# LilyPad_Rainbow_LED_v02.net
KiCad netlist of a schematic drawn in EAGLE
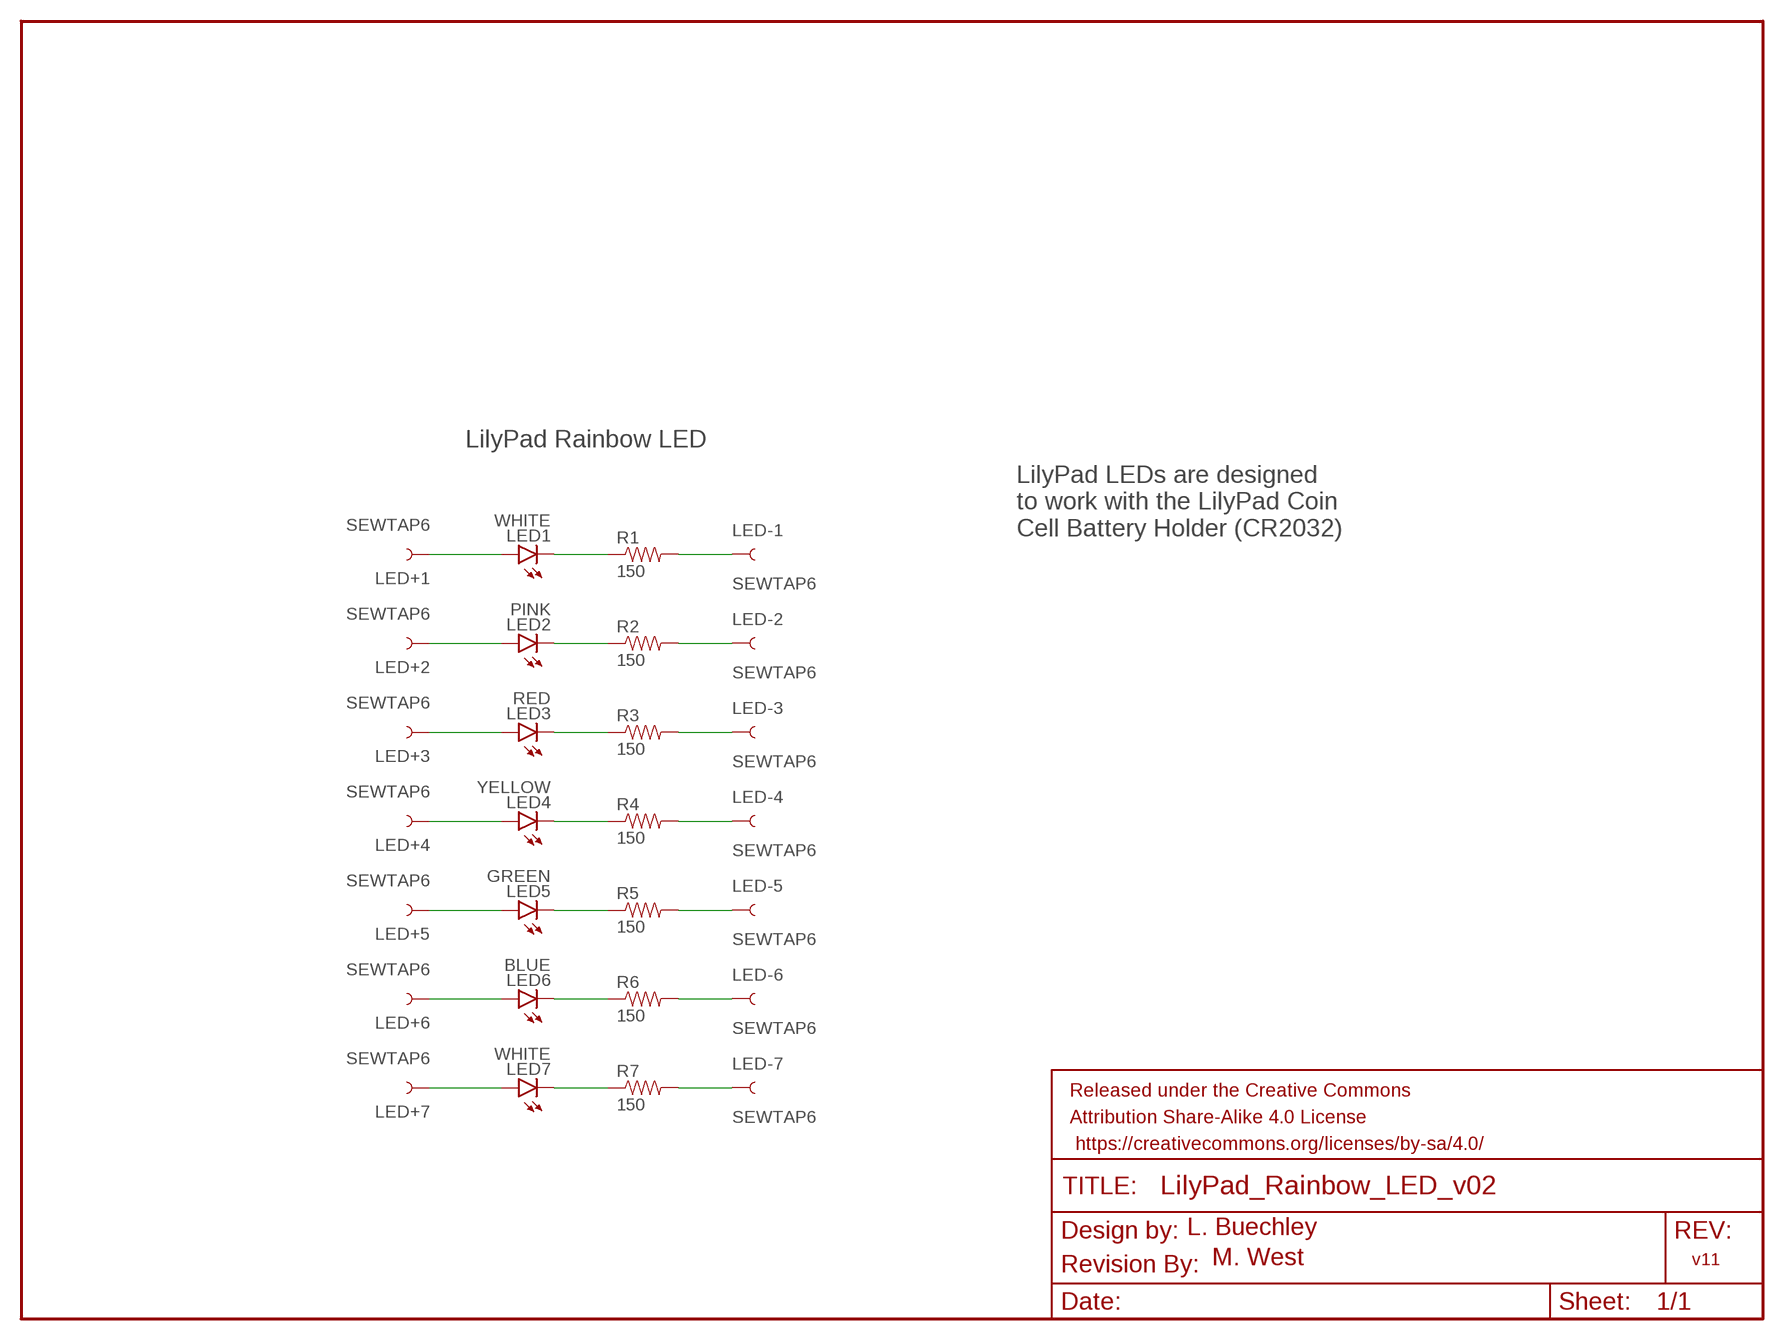
[diagram p0: schematic, sheet 1]

(export (version "E")
  (design (tool "Eeschema 10.0.6"))
  (components
    (comp (ref "FRAME1")
      (value "FRAME-LETTER")
      (footprint "eagle-import:CREATIVE_COMMONS")
      (libsource (lib "eagle-import") (part "FRAME-LETTER"))
    )
    (comp (ref "LED+1")
      (value "SEWTAP6")
      (footprint "eagle-import:PETAL-SMALL-2SIDE")
      (libsource (lib "eagle-import") (part "SEWTAP6"))
    )
    (comp (ref "LED+2")
      (value "SEWTAP6")
      (footprint "eagle-import:PETAL-SMALL-2SIDE")
      (libsource (lib "eagle-import") (part "SEWTAP6"))
    )
    (comp (ref "LED+3")
      (value "SEWTAP6")
      (footprint "eagle-import:PETAL-SMALL-2SIDE")
      (libsource (lib "eagle-import") (part "SEWTAP6"))
    )
    (comp (ref "LED+4")
      (value "SEWTAP6")
      (footprint "eagle-import:PETAL-SMALL-2SIDE")
      (libsource (lib "eagle-import") (part "SEWTAP6"))
    )
    (comp (ref "LED+5")
      (value "SEWTAP6")
      (footprint "eagle-import:PETAL-SMALL-2SIDE")
      (libsource (lib "eagle-import") (part "SEWTAP6"))
    )
    (comp (ref "LED+6")
      (value "SEWTAP6")
      (footprint "eagle-import:PETAL-SMALL-2SIDE")
      (libsource (lib "eagle-import") (part "SEWTAP6"))
    )
    (comp (ref "LED+7")
      (value "SEWTAP6")
      (footprint "eagle-import:PETAL-SMALL-2SIDE")
      (libsource (lib "eagle-import") (part "SEWTAP6"))
    )
    (comp (ref "LED-1")
      (value "SEWTAP6")
      (footprint "eagle-import:PETAL-SMALL-2SIDE")
      (libsource (lib "eagle-import") (part "SEWTAP6"))
    )
    (comp (ref "LED-2")
      (value "SEWTAP6")
      (footprint "eagle-import:PETAL-SMALL-2SIDE")
      (libsource (lib "eagle-import") (part "SEWTAP6"))
    )
    (comp (ref "LED-3")
      (value "SEWTAP6")
      (footprint "eagle-import:PETAL-SMALL-2SIDE")
      (libsource (lib "eagle-import") (part "SEWTAP6"))
    )
    (comp (ref "LED-4")
      (value "SEWTAP6")
      (footprint "eagle-import:PETAL-SMALL-2SIDE")
      (libsource (lib "eagle-import") (part "SEWTAP6"))
    )
    (comp (ref "LED-5")
      (value "SEWTAP6")
      (footprint "eagle-import:PETAL-SMALL-2SIDE")
      (libsource (lib "eagle-import") (part "SEWTAP6"))
    )
    (comp (ref "LED-6")
      (value "SEWTAP6")
      (footprint "eagle-import:PETAL-SMALL-2SIDE")
      (libsource (lib "eagle-import") (part "SEWTAP6"))
    )
    (comp (ref "LED-7")
      (value "SEWTAP6")
      (footprint "eagle-import:PETAL-SMALL-2SIDE")
      (libsource (lib "eagle-import") (part "SEWTAP6"))
    )
    (comp (ref "LED1")
      (value "WHITE")
      (footprint "eagle-import:LED-1206")
      (libsource (lib "eagle-import") (part "LED-WHITE1206"))
    )
    (comp (ref "LED2")
      (value "PINK")
      (footprint "eagle-import:LED-1206")
      (libsource (lib "eagle-import") (part "LED-PINK1206"))
    )
    (comp (ref "LED3")
      (value "RED")
      (footprint "eagle-import:LED-1206")
      (libsource (lib "eagle-import") (part "LED-REDLILYPAD"))
    )
    (comp (ref "LED4")
      (value "YELLOW")
      (footprint "eagle-import:LED-1206")
      (libsource (lib "eagle-import") (part "LED-YELLOWLILYPAD"))
    )
    (comp (ref "LED5")
      (value "GREEN")
      (footprint "eagle-import:LED-1206")
      (libsource (lib "eagle-import") (part "LED-GREENLILYPAD"))
    )
    (comp (ref "LED6")
      (value "BLUE")
      (footprint "eagle-import:LED-1206")
      (libsource (lib "eagle-import") (part "LED-BLUE1206"))
    )
    (comp (ref "LED7")
      (value "WHITE")
      (footprint "eagle-import:LED-1206")
      (libsource (lib "eagle-import") (part "LED-WHITE1206"))
    )
    (comp (ref "R1")
      (value "150")
      (footprint "eagle-import:0603-RES")
      (libsource (lib "eagle-import") (part "150OHM-1/10W-1%(0603)"))
    )
    (comp (ref "R2")
      (value "150")
      (footprint "eagle-import:0603-RES")
      (libsource (lib "eagle-import") (part "150OHM-1/10W-1%(0603)"))
    )
    (comp (ref "R3")
      (value "150")
      (footprint "eagle-import:0603-RES")
      (libsource (lib "eagle-import") (part "150OHM-1/10W-1%(0603)"))
    )
    (comp (ref "R4")
      (value "150")
      (footprint "eagle-import:0603-RES")
      (libsource (lib "eagle-import") (part "150OHM-1/10W-1%(0603)"))
    )
    (comp (ref "R5")
      (value "150")
      (footprint "eagle-import:0603-RES")
      (libsource (lib "eagle-import") (part "150OHM-1/10W-1%(0603)"))
    )
    (comp (ref "R6")
      (value "150")
      (footprint "eagle-import:0603-RES")
      (libsource (lib "eagle-import") (part "150OHM-1/10W-1%(0603)"))
    )
    (comp (ref "R7")
      (value "150")
      (footprint "eagle-import:0603-RES")
      (libsource (lib "eagle-import") (part "150OHM-1/10W-1%(0603)"))
    )
    (comp (ref "U$1")
      (value "REVISION")
      (footprint "eagle-import:REVISION")
      (libsource (lib "eagle-import") (part "REVISION"))
    )
  )
  (nets
    (net (code "1") (name "Net-(LED+1-Pad1)") (class "Default")
      (node (ref "LED+1") (pin "1") (pinfunction "1_1") (pintype "bidirectional"))
      (node (ref "LED1") (pin "A") (pinfunction "A_A") (pintype "passive"))
    )
    (net (code "2") (name "Net-(LED+2-Pad1)") (class "Default")
      (node (ref "LED+2") (pin "1") (pinfunction "1_1") (pintype "bidirectional"))
      (node (ref "LED2") (pin "A") (pinfunction "A_A") (pintype "passive"))
    )
    (net (code "3") (name "Net-(LED+3-Pad1)") (class "Default")
      (node (ref "LED+3") (pin "1") (pinfunction "1_1") (pintype "bidirectional"))
      (node (ref "LED3") (pin "A") (pinfunction "A_A") (pintype "passive"))
    )
    (net (code "4") (name "Net-(LED+4-Pad1)") (class "Default")
      (node (ref "LED+4") (pin "1") (pinfunction "1_1") (pintype "bidirectional"))
      (node (ref "LED4") (pin "A") (pinfunction "A_A") (pintype "passive"))
    )
    (net (code "5") (name "Net-(LED+5-Pad1)") (class "Default")
      (node (ref "LED+5") (pin "1") (pinfunction "1_1") (pintype "bidirectional"))
      (node (ref "LED5") (pin "A") (pinfunction "A_A") (pintype "passive"))
    )
    (net (code "6") (name "Net-(LED+6-Pad1)") (class "Default")
      (node (ref "LED+6") (pin "1") (pinfunction "1_1") (pintype "bidirectional"))
      (node (ref "LED6") (pin "A") (pinfunction "A_A") (pintype "passive"))
    )
    (net (code "7") (name "Net-(LED+7-Pad1)") (class "Default")
      (node (ref "LED+7") (pin "1") (pinfunction "1_1") (pintype "bidirectional"))
      (node (ref "LED7") (pin "A") (pinfunction "A_A") (pintype "passive"))
    )
    (net (code "8") (name "Net-(LED-1-Pad1)") (class "Default")
      (node (ref "LED-1") (pin "1") (pinfunction "1_1") (pintype "bidirectional"))
      (node (ref "R1") (pin "2") (pinfunction "2_2") (pintype "passive"))
    )
    (net (code "9") (name "Net-(LED-2-Pad1)") (class "Default")
      (node (ref "LED-2") (pin "1") (pinfunction "1_1") (pintype "bidirectional"))
      (node (ref "R2") (pin "2") (pinfunction "2_2") (pintype "passive"))
    )
    (net (code "10") (name "Net-(LED-3-Pad1)") (class "Default")
      (node (ref "LED-3") (pin "1") (pinfunction "1_1") (pintype "bidirectional"))
      (node (ref "R3") (pin "2") (pinfunction "2_2") (pintype "passive"))
    )
    (net (code "11") (name "Net-(LED-4-Pad1)") (class "Default")
      (node (ref "LED-4") (pin "1") (pinfunction "1_1") (pintype "bidirectional"))
      (node (ref "R4") (pin "2") (pinfunction "2_2") (pintype "passive"))
    )
    (net (code "12") (name "Net-(LED-5-Pad1)") (class "Default")
      (node (ref "LED-5") (pin "1") (pinfunction "1_1") (pintype "bidirectional"))
      (node (ref "R5") (pin "2") (pinfunction "2_2") (pintype "passive"))
    )
    (net (code "13") (name "Net-(LED-6-Pad1)") (class "Default")
      (node (ref "LED-6") (pin "1") (pinfunction "1_1") (pintype "bidirectional"))
      (node (ref "R6") (pin "2") (pinfunction "2_2") (pintype "passive"))
    )
    (net (code "14") (name "Net-(LED-7-Pad1)") (class "Default")
      (node (ref "LED-7") (pin "1") (pinfunction "1_1") (pintype "bidirectional"))
      (node (ref "R7") (pin "2") (pinfunction "2_2") (pintype "passive"))
    )
    (net (code "15") (name "Net-(LED1-PadC)") (class "Default")
      (node (ref "LED1") (pin "C") (pinfunction "C_C") (pintype "passive"))
      (node (ref "R1") (pin "1") (pinfunction "1_1") (pintype "passive"))
    )
    (net (code "16") (name "Net-(LED2-PadC)") (class "Default")
      (node (ref "LED2") (pin "C") (pinfunction "C_C") (pintype "passive"))
      (node (ref "R2") (pin "1") (pinfunction "1_1") (pintype "passive"))
    )
    (net (code "17") (name "Net-(LED3-PadC)") (class "Default")
      (node (ref "LED3") (pin "C") (pinfunction "C_C") (pintype "passive"))
      (node (ref "R3") (pin "1") (pinfunction "1_1") (pintype "passive"))
    )
    (net (code "18") (name "Net-(LED4-PadC)") (class "Default")
      (node (ref "LED4") (pin "C") (pinfunction "C_C") (pintype "passive"))
      (node (ref "R4") (pin "1") (pinfunction "1_1") (pintype "passive"))
    )
    (net (code "19") (name "Net-(LED5-PadC)") (class "Default")
      (node (ref "LED5") (pin "C") (pinfunction "C_C") (pintype "passive"))
      (node (ref "R5") (pin "1") (pinfunction "1_1") (pintype "passive"))
    )
    (net (code "20") (name "Net-(LED6-PadC)") (class "Default")
      (node (ref "LED6") (pin "C") (pinfunction "C_C") (pintype "passive"))
      (node (ref "R6") (pin "1") (pinfunction "1_1") (pintype "passive"))
    )
    (net (code "21") (name "Net-(LED7-PadC)") (class "Default")
      (node (ref "LED7") (pin "C") (pinfunction "C_C") (pintype "passive"))
      (node (ref "R7") (pin "1") (pinfunction "1_1") (pintype "passive"))
    )
  )
)
